# ProPrj_usb__2025-12-14-12-14-50.net
KiCad netlist of a schematic drawn in EasyEDA Pro
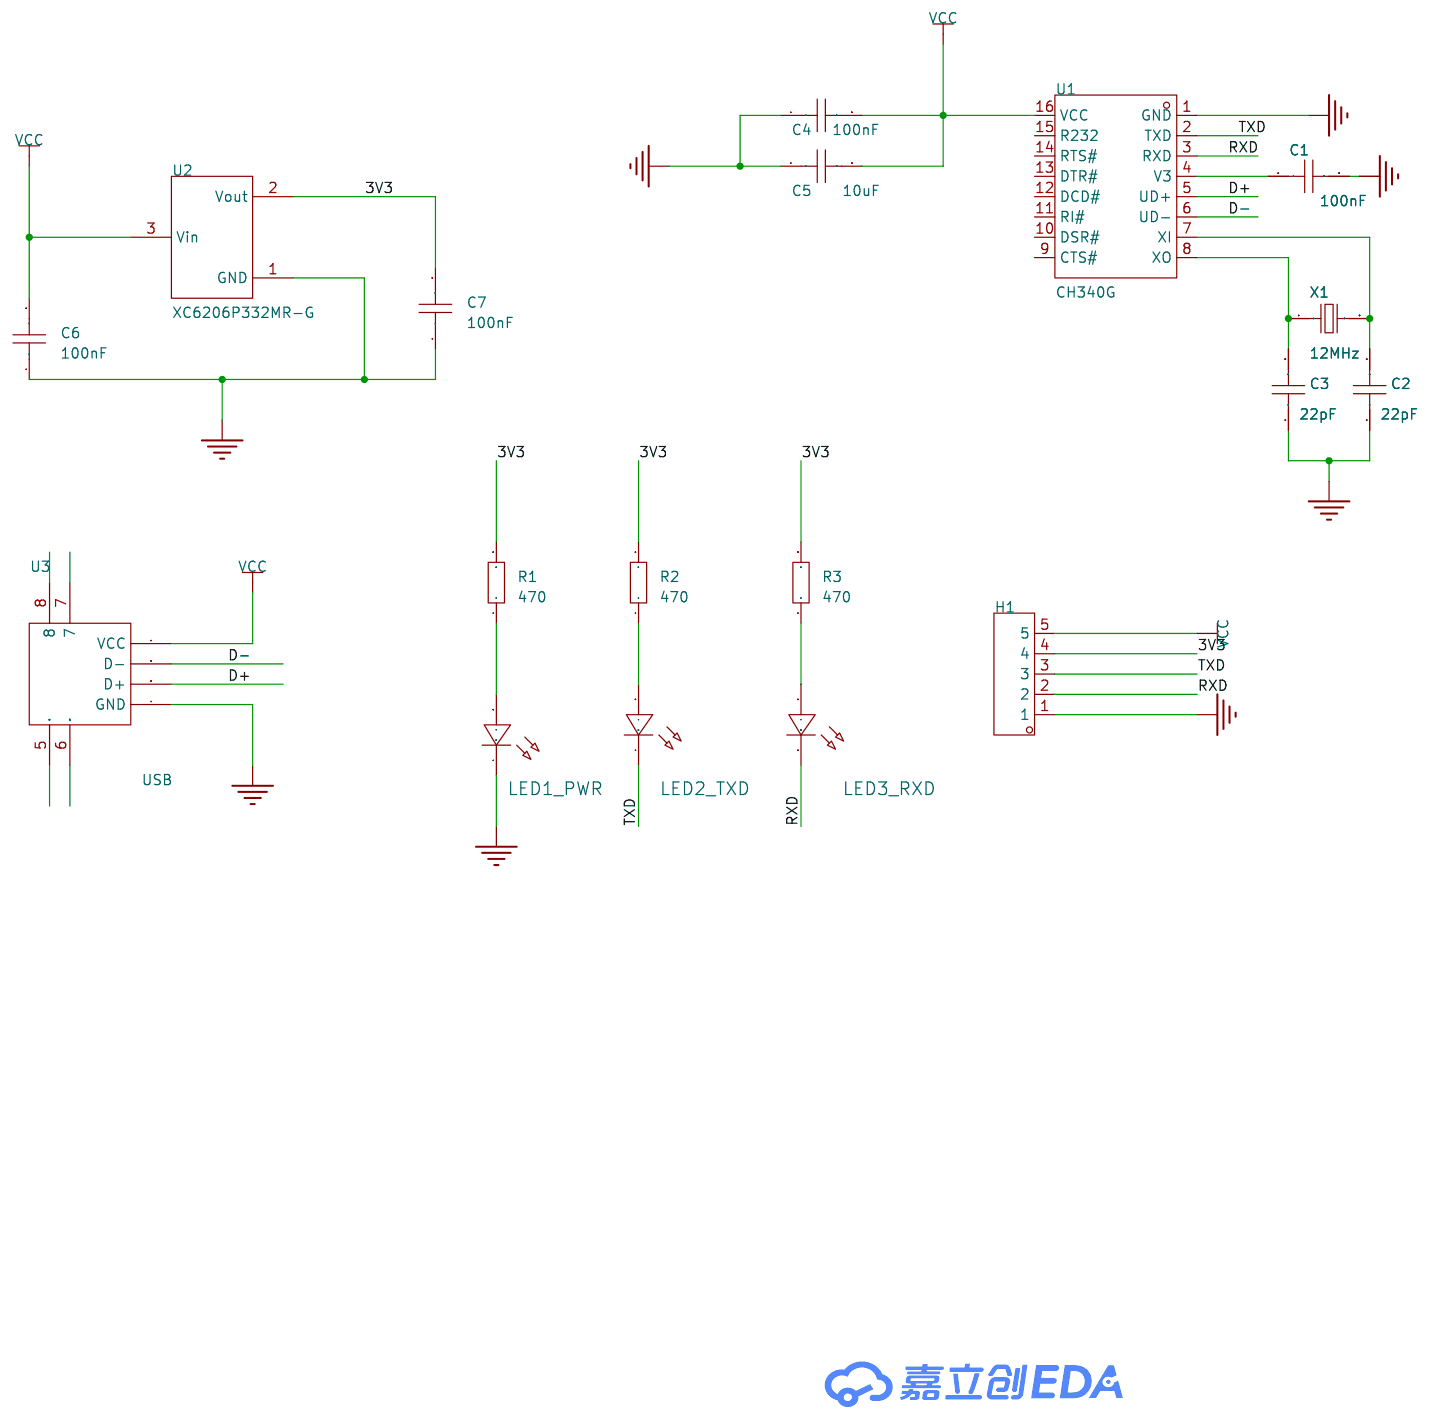
[diagram p0: schematic sheet]

(export (version "E")
  (design (tool "Eeschema 10.0.6"))
  (components
    (comp (ref "C1")
      (value "100nF")
      (footprint "easyedapro:C0603")
      (libsource (lib "easyedapro") (part "Capacitance"))
    )
    (comp (ref "C2")
      (value "22pF")
      (footprint "easyedapro:C0603")
      (libsource (lib "easyedapro") (part "Capacitance"))
    )
    (comp (ref "C3")
      (value "22pF")
      (footprint "easyedapro:C0603")
      (libsource (lib "easyedapro") (part "Capacitance"))
    )
    (comp (ref "C4")
      (value "100nF")
      (footprint "easyedapro:C0603")
      (libsource (lib "easyedapro") (part "Capacitance"))
    )
    (comp (ref "C5")
      (value "10uF")
      (footprint "easyedapro:C0603")
      (libsource (lib "easyedapro") (part "Capacitance"))
    )
    (comp (ref "C6")
      (value "100nF")
      (footprint "easyedapro:C0603")
      (libsource (lib "easyedapro") (part "Capacitance"))
    )
    (comp (ref "C7")
      (value "100nF")
      (footprint "easyedapro:C0603")
      (libsource (lib "easyedapro") (part "Capacitance"))
    )
    (comp (ref "H1")
      (value "~")
      (footprint "easyedapro:HDR-TH_5P-P2.54-V-M")
      (libsource (lib "easyedapro") (part "MTP125-1105S1"))
    )
    (comp (ref "LED1_PWR")
      (value "~")
      (footprint "easyedapro:LED_0603")
      (libsource (lib "easyedapro") (part "LED_R"))
    )
    (comp (ref "LED2_TXD")
      (value "~")
      (footprint "easyedapro:LED_0603")
      (libsource (lib "easyedapro") (part "LED_R"))
    )
    (comp (ref "LED3_RXD")
      (value "~")
      (footprint "easyedapro:LED_0603")
      (libsource (lib "easyedapro") (part "LED_R"))
    )
    (comp (ref "R1") (value "470") (footprint "easyedapro:R0603") (libsource (lib "easyedapro") (part "电阻")))
    (comp (ref "R2") (value "470") (footprint "easyedapro:R0603") (libsource (lib "easyedapro") (part "电阻")))
    (comp (ref "R3") (value "470") (footprint "easyedapro:R0603") (libsource (lib "easyedapro") (part "电阻")))
    (comp (ref "U1")
      (value "CH340G")
      (footprint "easyedapro:SOIC-16_L9.9-W3.9-P1.27-LS6.0-BL")
      (description "应用功能:USB转UART;接口协议:USB 2.0;数据速率:2Mbps;")
      (fields (field (name "Manufacturer") "WCH(南京沁恒)"))
      (libsource (lib "easyedapro") (part "CH340G"))
    )
    (comp (ref "U2")
      (value "XC6206P332MR-G")
      (footprint "easyedapro:SOT-23-3_L2.9-W1.6-P1.90-LS2.8-BR")
      (description "输出类型:固定;工作电压:6V;输出电压:3.3V;输出电流:200mA;电源纹波抑制比(PSRR):-;输出极性:正极;")
      (fields (field (name "Manufacturer") "TOREX(特瑞仕)"))
      (libsource (lib "easyedapro") (part "XC6206P332MR"))
    )
    (comp (ref "U3")
      (value "USB")
      (footprint "easyedapro:USB-SMD_USB_1")
      (libsource (lib "easyedapro") (part "USB"))
    )
    (comp (ref "X1")
      (value "12MHz")
      (footprint "easyedapro:CRYSTAL-SMD_L5.0-W3.2")
      (description "晶振类型:贴片晶振;频率:12MHz;常温频差:±20ppm;负载电容:20pF;频率稳定度:±30ppm;")
      (fields
        (field (name "Manufacturer Part") "XC53G2-12.000-F20LJDT")
        (field (name "Manufacturer") "HCI(杭晶)")
      )
      (libsource (lib "easyedapro") (part "XC53G2-12.000-F20LJDT"))
    )
  )
  (nets
    (net (code "1") (name "/3V3") (class "Default")
      (node (ref "C7") (pin "2") (pinfunction "2_2") (pintype "input"))
      (node (ref "H1") (pin "4") (pinfunction "4_4") (pintype "unspecified"))
      (node (ref "R1") (pin "2") (pinfunction "2_2") (pintype "input"))
      (node (ref "R2") (pin "2") (pinfunction "2_2") (pintype "input"))
      (node (ref "R3") (pin "2") (pinfunction "2_2") (pintype "input"))
      (node (ref "U2") (pin "2") (pinfunction "Vout_2") (pintype "unspecified"))
    )
    (net (code "2") (name "/D+") (class "Default")
      (node (ref "U1") (pin "5") (pinfunction "UD+_5") (pintype "unspecified"))
      (node (ref "U3") (pin "3") (pinfunction "D+_3") (pintype "input"))
    )
    (net (code "3") (name "/D-") (class "Default")
      (node (ref "U1") (pin "6") (pinfunction "UD-_6") (pintype "unspecified"))
      (node (ref "U3") (pin "2") (pinfunction "D-_2") (pintype "input"))
    )
    (net (code "4") (name "/RXD") (class "Default")
      (node (ref "H1") (pin "2") (pinfunction "2_2") (pintype "unspecified"))
      (node (ref "LED3_RXD") (pin "1") (pinfunction "C_1") (pintype "input"))
      (node (ref "U1") (pin "3") (pinfunction "RXD_3") (pintype "unspecified"))
    )
    (net (code "5") (name "/TXD") (class "Default")
      (node (ref "H1") (pin "3") (pinfunction "3_3") (pintype "unspecified"))
      (node (ref "LED2_TXD") (pin "1") (pinfunction "C_1") (pintype "input"))
      (node (ref "U1") (pin "2") (pinfunction "TXD_2") (pintype "unspecified"))
    )
    (net (code "6") (name "GND") (class "Default")
      (node (ref "C1") (pin "2") (pinfunction "2_2") (pintype "input"))
      (node (ref "C2") (pin "1") (pinfunction "1_1") (pintype "input"))
      (node (ref "C3") (pin "1") (pinfunction "1_1") (pintype "input"))
      (node (ref "C4") (pin "1") (pinfunction "1_1") (pintype "input"))
      (node (ref "C5") (pin "1") (pinfunction "1_1") (pintype "input"))
      (node (ref "C6") (pin "1") (pinfunction "1_1") (pintype "input"))
      (node (ref "C7") (pin "1") (pinfunction "1_1") (pintype "input"))
      (node (ref "H1") (pin "1") (pinfunction "1_1") (pintype "unspecified"))
      (node (ref "LED1_PWR") (pin "1") (pinfunction "C_1") (pintype "input"))
      (node (ref "U1") (pin "1") (pinfunction "GND_1") (pintype "unspecified"))
      (node (ref "U2") (pin "1") (pinfunction "GND_1") (pintype "unspecified"))
      (node (ref "U3") (pin "4") (pinfunction "GND_4") (pintype "input"))
    )
    (net (code "7") (name "Net-(LED1_PWR-A)") (class "Default")
      (node (ref "LED1_PWR") (pin "2") (pinfunction "A_2") (pintype "input"))
      (node (ref "R1") (pin "1") (pinfunction "1_1") (pintype "input"))
    )
    (net (code "8") (name "Net-(LED2_TXD-A)") (class "Default")
      (node (ref "LED2_TXD") (pin "2") (pinfunction "A_2") (pintype "input"))
      (node (ref "R2") (pin "1") (pinfunction "1_1") (pintype "input"))
    )
    (net (code "9") (name "Net-(LED3_RXD-A)") (class "Default")
      (node (ref "LED3_RXD") (pin "2") (pinfunction "A_2") (pintype "input"))
      (node (ref "R3") (pin "1") (pinfunction "1_1") (pintype "input"))
    )
    (net (code "10") (name "Net-(U1-V3)") (class "Default")
      (node (ref "C1") (pin "1") (pinfunction "1_1") (pintype "input"))
      (node (ref "U1") (pin "4") (pinfunction "V3_4") (pintype "unspecified"))
    )
    (net (code "11") (name "Net-(U1-XI)") (class "Default")
      (node (ref "C2") (pin "2") (pinfunction "2_2") (pintype "input"))
      (node (ref "U1") (pin "7") (pinfunction "XI_7") (pintype "unspecified"))
      (node (ref "X1") (pin "2") (pinfunction "2_2") (pintype "unspecified"))
    )
    (net (code "12") (name "Net-(U1-XO)") (class "Default")
      (node (ref "C3") (pin "2") (pinfunction "2_2") (pintype "input"))
      (node (ref "U1") (pin "8") (pinfunction "XO_8") (pintype "unspecified"))
      (node (ref "X1") (pin "1") (pinfunction "1_1") (pintype "unspecified"))
    )
    (net (code "13") (name "VCC") (class "Default")
      (node (ref "C4") (pin "2") (pinfunction "2_2") (pintype "input"))
      (node (ref "C5") (pin "2") (pinfunction "2_2") (pintype "input"))
      (node (ref "C6") (pin "2") (pinfunction "2_2") (pintype "input"))
      (node (ref "H1") (pin "5") (pinfunction "5_5") (pintype "unspecified"))
      (node (ref "U1") (pin "16") (pinfunction "VCC_16") (pintype "unspecified"))
      (node (ref "U2") (pin "3") (pinfunction "Vin_3") (pintype "unspecified"))
      (node (ref "U3") (pin "1") (pinfunction "VCC_1") (pintype "input"))
    )
    (net (code "14") (name "unconnected-(U1-CTS#-Pad9)") (class "Default")
      (node (ref "U1") (pin "9") (pinfunction "CTS#_9") (pintype "unspecified"))
    )
    (net (code "15") (name "unconnected-(U1-DCD#-Pad12)") (class "Default")
      (node (ref "U1") (pin "12") (pinfunction "DCD#_12") (pintype "unspecified"))
    )
    (net (code "16") (name "unconnected-(U1-DSR#-Pad10)") (class "Default")
      (node (ref "U1") (pin "10") (pinfunction "DSR#_10") (pintype "unspecified"))
    )
    (net (code "17") (name "unconnected-(U1-DTR#-Pad13)") (class "Default")
      (node (ref "U1") (pin "13") (pinfunction "DTR#_13") (pintype "unspecified"))
    )
    (net (code "18") (name "unconnected-(U1-R232-Pad15)") (class "Default")
      (node (ref "U1") (pin "15") (pinfunction "R232_15") (pintype "unspecified"))
    )
    (net (code "19") (name "unconnected-(U1-RI#-Pad11)") (class "Default")
      (node (ref "U1") (pin "11") (pinfunction "RI#_11") (pintype "unspecified"))
    )
    (net (code "20") (name "unconnected-(U1-RTS#-Pad14)") (class "Default")
      (node (ref "U1") (pin "14") (pinfunction "RTS#_14") (pintype "unspecified"))
    )
    (net (code "21") (name "unconnected-(U3-Pad7)") (class "Default")
      (node (ref "U3") (pin "7") (pinfunction "7_7") (pintype "unspecified"))
    )
    (net (code "22") (name "unconnected-(U3-Pad8)") (class "Default")
      (node (ref "U3") (pin "8") (pinfunction "8_8") (pintype "unspecified"))
    )
    (net (code "23") (name "unconnected-(U3-SH1-Pad5)") (class "Default")
      (node (ref "U3") (pin "5") (pinfunction "SH1_5") (pintype "unspecified"))
    )
    (net (code "24") (name "unconnected-(U3-SH2-Pad6)") (class "Default")
      (node (ref "U3") (pin "6") (pinfunction "SH2_6") (pintype "unspecified"))
    )
  )
)
